# PowerModuleCell.net
KiCad netlist of a schematic drawn in Altium Designer
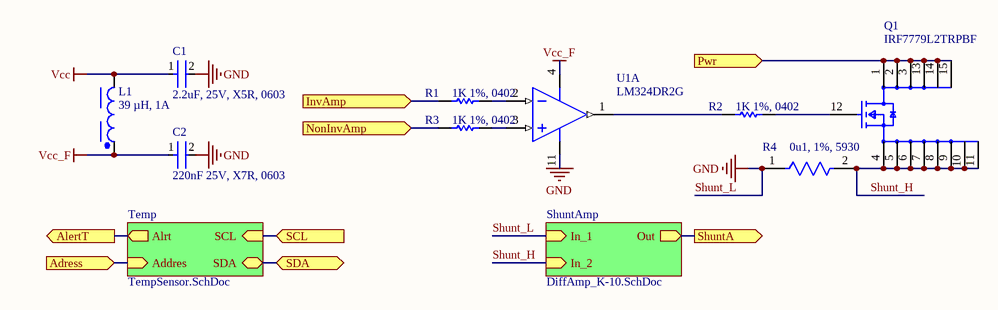
[diagram p0: PowerModuleCell.SchDoc]

(export (version "E")
  (design (tool "Eeschema 10.0.6"))
  (components
    (comp (ref "C1")
      (value "2.2uF, 25V, X5R, 0603")
      (footprint "FP-GRM188-0_1-e0_2_0_5-MFG")
      (description "Chip Multilayer Ceramic Capacitors for General Purpose, 0603, 2.2uF, X5R, 15%, 10%, 25V")
      (fields (field (name "TOLERANCE") "10%") (field (name "VOLTAGE") "25V"))
      (libsource (lib "Altium Content Vault") (part "11868f565c42a9108669ba33697ecf6"))
    )
    (comp (ref "C2")
      (value "220nF 25V, X7R, 0603")
      (footprint "FP-GCM188-0_1-IPC_B")
      (description "Ceramic Capacitor for Automotive 220nF  ±10% 25VDC X7R 0603 Paper T/R")
      (fields (field (name "VOLTAGE") "25V") (field (name "TOLERANCE") "10%"))
      (libsource (lib "Altium Content Vault") (part "02cd4be3c70576c341d710602a673aa"))
    )
    (comp (ref "L1")
      (value "39 µH, 1A")
      (footprint "WE-PD_7345")
      (fields (field (name "TOLERANCE") "20%"))
      (libsource (lib "Altium Content Vault") (part "Inductor - 2"))
    )
    (comp (ref "Q1")
      (value "IRF7779L2TRPBF")
      (footprint "FP-MG-WDSON-11-MFG")
      (description "MOSFET N-CH 150V 375A DIRECTFET")
      (libsource (lib "Altium Content Vault") (part "931aa336c46c4a6bee47271e78b4879"))
    )
    (comp (ref "R1")
      (value "1K 1%, 0402")
      (footprint "RESC1005X40X25NL05T05")
      (description "Chip Resistor, 1 KOhm, +/- 1%, 100 mW, -55 to 155 degC, 0402 (1005 Metric), RoHS, Tape and Reel")
      (fields (field (name "PARTNUMBER") "ERJ-2RKF1001X") (field (name "MANUFACTURER") "Basic Passives"))
      (libsource (lib "Altium Content Vault") (part "RES-2"))
    )
    (comp (ref "R2")
      (value "1K 1%, 0402")
      (footprint "RESC1005X40X25NL05T05")
      (description "Chip Resistor, 1 KOhm, +/- 1%, 100 mW, -55 to 155 degC, 0402 (1005 Metric), RoHS, Tape and Reel")
      (fields (field (name "PARTNUMBER") "ERJ-2RKF1001X") (field (name "MANUFACTURER") "Basic Passives"))
      (libsource (lib "Altium Content Vault") (part "RES-2"))
    )
    (comp (ref "R3")
      (value "1K 1%, 0402")
      (footprint "RESC1005X40X25NL05T05")
      (description "Chip Resistor, 1 KOhm, +/- 1%, 100 mW, -55 to 155 degC, 0402 (1005 Metric), RoHS, Tape and Reel")
      (fields (field (name "PARTNUMBER") "ERJ-2RKF1001X") (field (name "MANUFACTURER") "Basic Passives"))
      (libsource (lib "Altium Content Vault") (part "RES-2"))
    )
    (comp (ref "R4")
      (value "0u1, 1%, 5930")
      (footprint "FP-CSS2H-5930K-1L00F-MFG")
      (description "CSS2H-5930K-1L00F Res Metal Strip 5930 0.001 Ohm 1% 9W ±50ppm/C Pad SMD Automotive T/R")
      (fields (field (name "TOLERANCE") "1%"))
      (libsource (lib "Altium Content Vault") (part "1029c3af85768c4190bb7ad29bc67b5"))
    )
    (comp (ref "U1")
      (value "LM324DR2G")
      (footprint "ONSC-SOIC-14-751A-03_V")
      (fields (field (name "MANUFACTURER") "On Semiconductor"))
      (libsource (lib "Altium Content Vault") (part "ONSC-LM224_324_2902_NCV2902-14"))
    )
  )
  (nets
    (net (code "3") (name "/InvAmp") (class "Default")
      (node (ref "R1") (pin "1") (pinfunction "1_1") (pintype "passive"))
    )
    (net (code "4") (name "/NonInvAmp") (class "Default")
      (node (ref "R3") (pin "1") (pinfunction "1_1") (pintype "passive"))
    )
    (net (code "5") (name "/Pwr") (class "Default")
      (node (ref "Q1") (pin "1") (pinfunction "Drain_1") (pintype "passive"))
      (node (ref "Q1") (pin "13") (pinfunction "Drain_13") (pintype "passive"))
      (node (ref "Q1") (pin "14") (pinfunction "Drain_14") (pintype "passive"))
      (node (ref "Q1") (pin "15") (pinfunction "Drain_15") (pintype "passive"))
      (node (ref "Q1") (pin "2") (pinfunction "Drain_2") (pintype "passive"))
      (node (ref "Q1") (pin "3") (pinfunction "Drain_3") (pintype "passive"))
    )
    (net (code "9") (name "/Shunt_H") (class "Default")
      (node (ref "Q1") (pin "10") (pinfunction "Source_10") (pintype "passive"))
      (node (ref "Q1") (pin "11") (pinfunction "Source_11") (pintype "passive"))
      (node (ref "Q1") (pin "4") (pinfunction "Source_4") (pintype "passive"))
      (node (ref "Q1") (pin "5") (pinfunction "Source_5") (pintype "passive"))
      (node (ref "Q1") (pin "6") (pinfunction "Source_6") (pintype "passive"))
      (node (ref "Q1") (pin "7") (pinfunction "Source_7") (pintype "passive"))
      (node (ref "Q1") (pin "8") (pinfunction "Source_8") (pintype "passive"))
      (node (ref "Q1") (pin "9") (pinfunction "Source_9") (pintype "passive"))
      (node (ref "R4") (pin "2") (pinfunction "2_2") (pintype "passive"))
    )
    (net (code "10") (name "GND") (class "Default")
      (node (ref "C1") (pin "2") (pinfunction "2_2") (pintype "passive"))
      (node (ref "C2") (pin "2") (pinfunction "2_2") (pintype "passive"))
      (node (ref "R4") (pin "1") (pinfunction "1_1") (pintype "passive"))
      (node (ref "U1") (pin "11") (pinfunction "VEE/GND_11") (pintype "power_in"))
    )
    (net (code "11") (name "Net-(Q1-Gate)") (class "Default")
      (node (ref "Q1") (pin "12") (pinfunction "Gate_12") (pintype "passive"))
      (node (ref "R2") (pin "2") (pinfunction "2_2") (pintype "passive"))
    )
    (net (code "12") (name "Net-(U1A-IN1+)") (class "Default")
      (node (ref "R3") (pin "2") (pinfunction "2_2") (pintype "passive"))
      (node (ref "U1") (pin "3") (pinfunction "IN1+_3") (pintype "input"))
    )
    (net (code "13") (name "Net-(U1A-IN1-)") (class "Default")
      (node (ref "R1") (pin "2") (pinfunction "2_2") (pintype "passive"))
      (node (ref "U1") (pin "2") (pinfunction "IN1-_2") (pintype "input"))
    )
    (net (code "14") (name "Net-(U1A-OUT1)") (class "Default")
      (node (ref "R2") (pin "1") (pinfunction "1_1") (pintype "passive"))
      (node (ref "U1") (pin "1") (pinfunction "OUT1_1") (pintype "output"))
    )
    (net (code "15") (name "Vcc") (class "Default")
      (node (ref "C1") (pin "1") (pinfunction "1_1") (pintype "passive"))
      (node (ref "L1") (pin "2") (pinfunction "2_2") (pintype "passive"))
    )
    (net (code "16") (name "Vcc_F") (class "Default")
      (node (ref "C2") (pin "1") (pinfunction "1_1") (pintype "passive"))
      (node (ref "L1") (pin "1") (pinfunction "1_1") (pintype "passive"))
      (node (ref "U1") (pin "4") (pinfunction "VCC_4") (pintype "power_in"))
    )
  )
)
